# MAXREFDES117_APPS_P1.net
KiCad netlist of a schematic drawn in Altium Designer
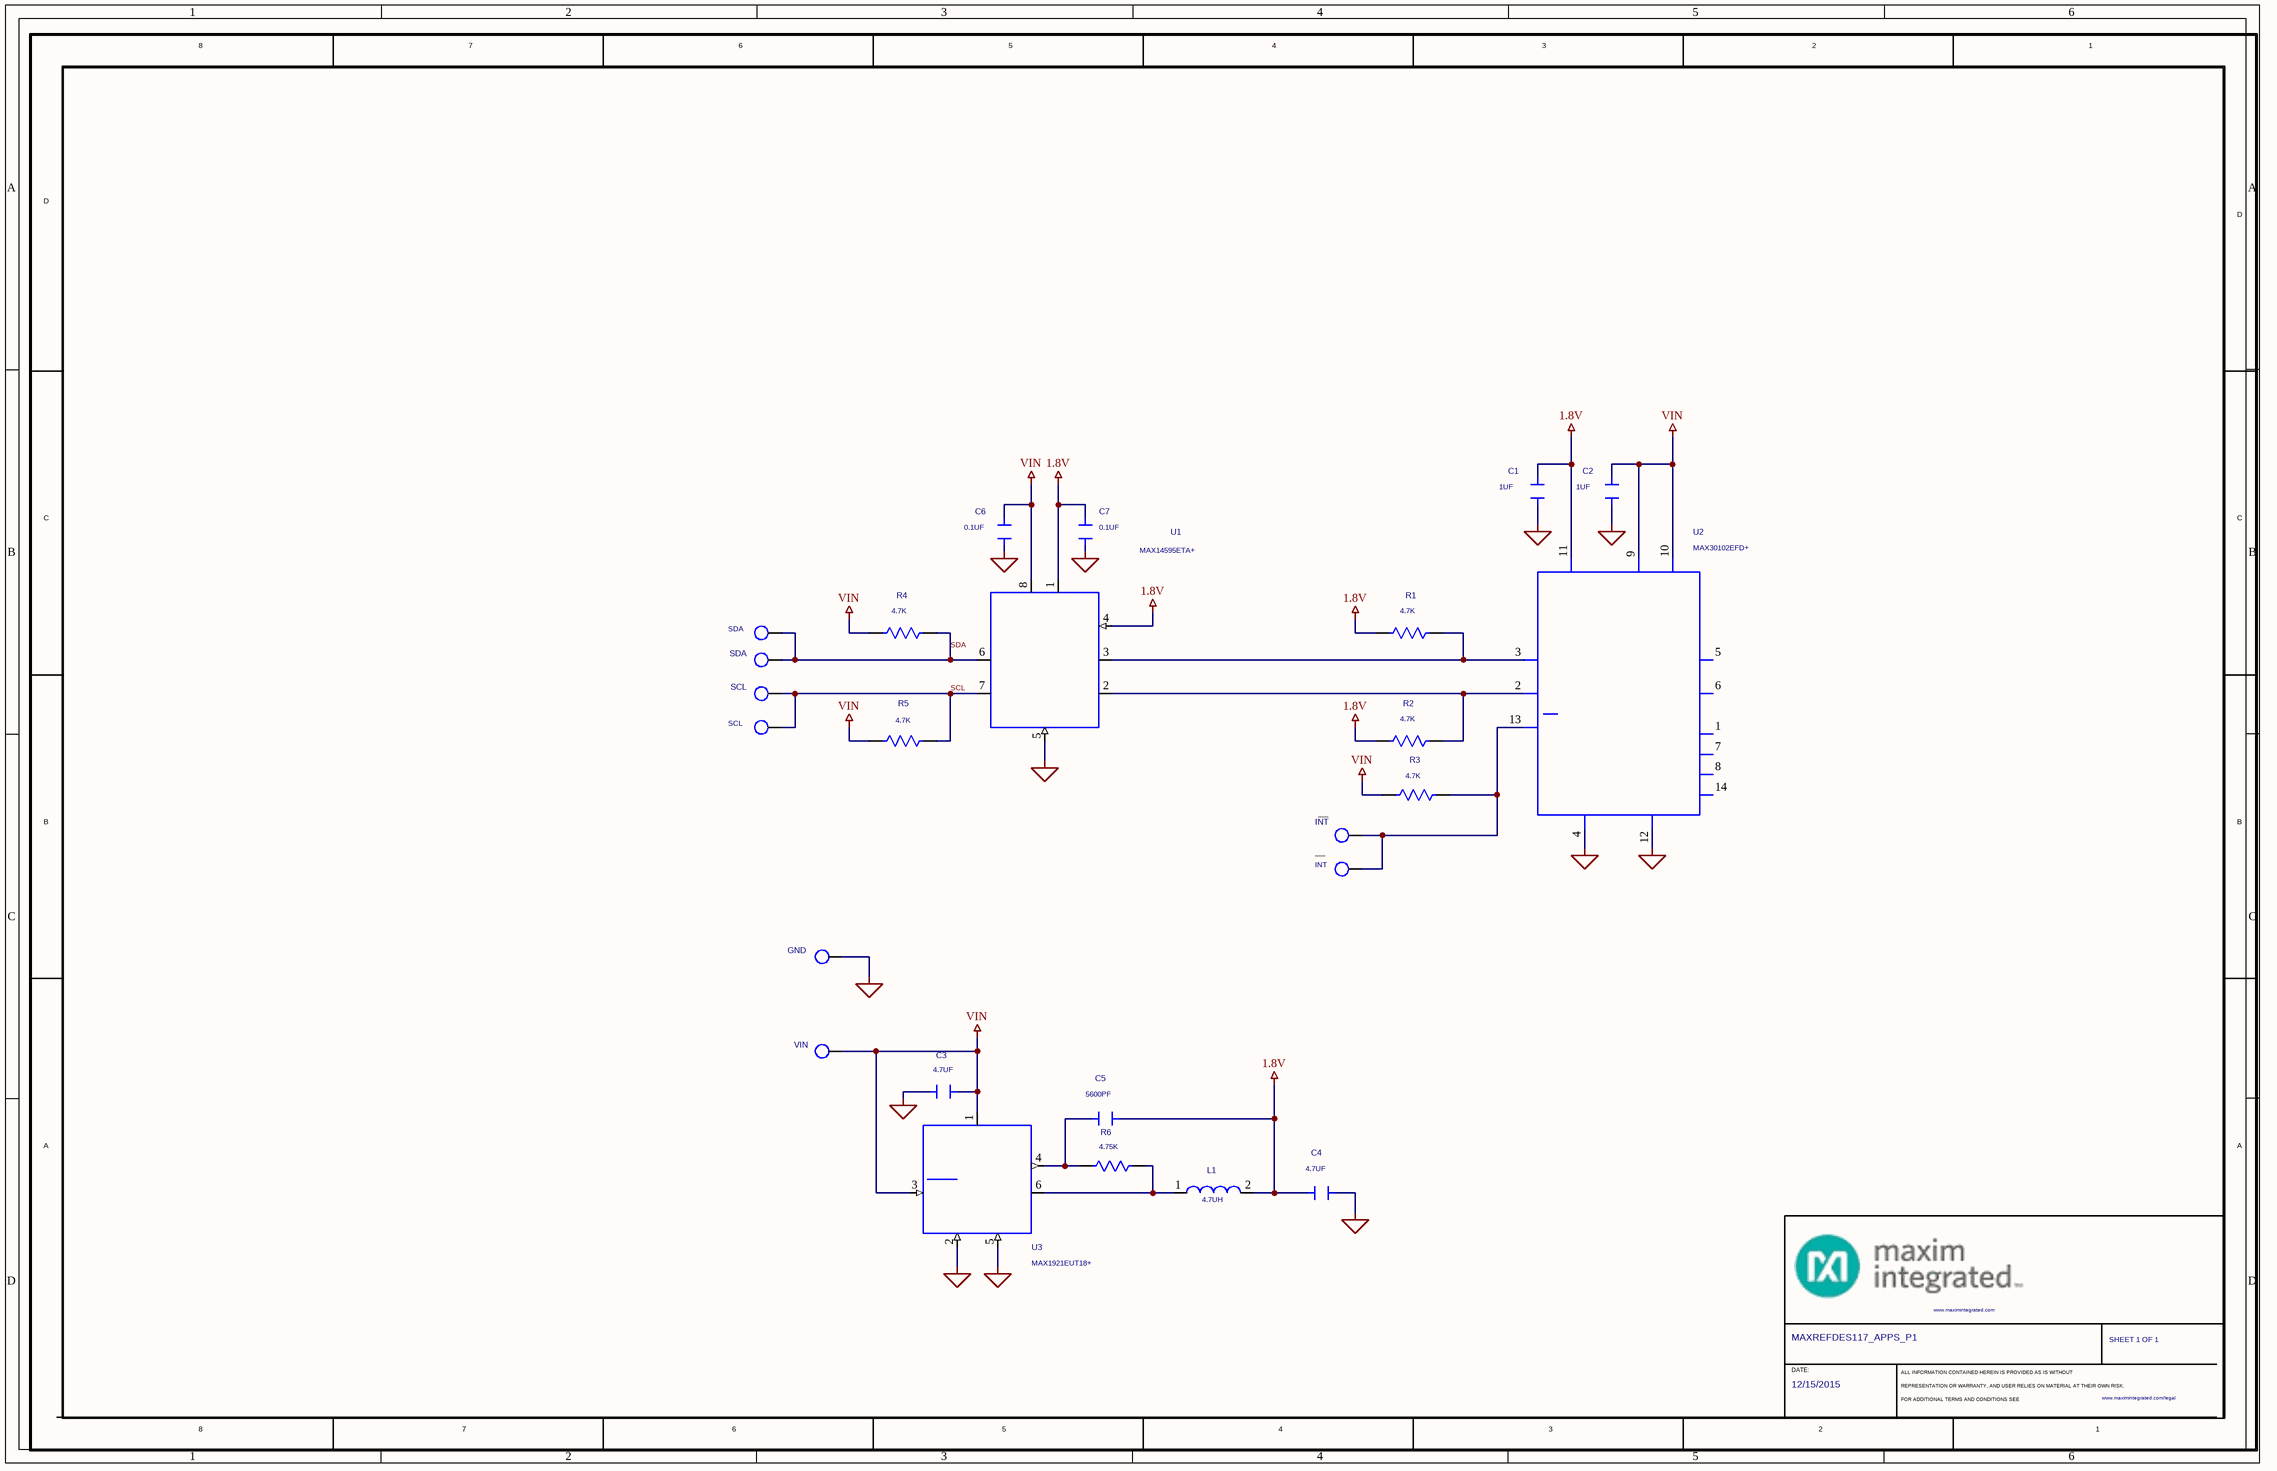
[diagram p0: MAXREFDES117_APPS_P1.SchDoc]

(export (version "E")
  (design (tool "Eeschema 10.0.6"))
  (components
    (comp (ref "*")
      (value "MAXIM_B_SIZE_CF")
      (fields
        (field (name "CUSTOM_TXT_CDS21") "SHEET 1 OF 1")
        (field (name "PROJECT_TITLE") "MAXREFDES117_APPS_P1")
        (field (name "LEAGAL_WEBLINK") "www.maximintegrated.com/legal")
        (field (name "WEBLINK1") "www.maximintegrated.com")
        (field (name "DATE") "12/15/2015")
      )
      (libsource (lib "*") (part "MAXIM_B_SIZE_CF"))
    )
    (comp (ref "C1")
      (value "1UF")
      (footprint "0402")
      (description "CAP; SMT (0402); 1UF; 10%; 10V; X5R; CERAMIC")
      (fields (field (name "TOLERANCE") "10%") (field (name "MANUFACTURER") "VENKEL LTD.;MURATA"))
      (libsource (lib "*") (part "CAP_NP#1"))
    )
    (comp (ref "C2")
      (value "1UF")
      (footprint "0402")
      (description "CAP; SMT (0402); 1UF; 10%; 10V; X5R; CERAMIC")
      (fields (field (name "TOLERANCE") "10%") (field (name "MANUFACTURER") "VENKEL LTD.;MURATA"))
      (libsource (lib "*") (part "CAP_NP#1"))
    )
    (comp (ref "C3")
      (value "4.7UF")
      (footprint "0402")
      (description "CAP; SMT (0402); 4.7UF; 20%; 4V; X5R; CERAMIC")
      (fields (field (name "TOLERANCE") "20%") (field (name "MANUFACTURER") "KEMET;MURATA;MURATA"))
      (libsource (lib "*") (part "CAP_NP"))
    )
    (comp (ref "C4")
      (value "4.7UF")
      (footprint "0402")
      (description "CAP; SMT (0402); 4.7UF; 20%; 4V; X5R; CERAMIC")
      (fields (field (name "TOLERANCE") "20%") (field (name "MANUFACTURER") "KEMET;MURATA;MURATA"))
      (libsource (lib "*") (part "CAP_NP"))
    )
    (comp (ref "C5")
      (value "5600PF")
      (footprint "0402")
      (description "CAP; SMT (0402); 5600PF; 10%; 25V; X7R; CERAMIC")
      (fields (field (name "TOLERANCE") "10%") (field (name "MANUFACTURER") "VENKEL LTD;MURATA;MURATA"))
      (libsource (lib "*") (part "CAP_NP"))
    )
    (comp (ref "C6")
      (value "0.1UF")
      (footprint "0402")
      (description "CAP; SMT (0402); 0.1UF; 10%; 16V; X7R; CERAMIC")
      (fields (field (name "TOLERANCE") "10%"))
      (libsource (lib "*") (part "CAP_NP#1"))
    )
    (comp (ref "C7")
      (value "0.1UF")
      (footprint "0402")
      (description "CAP; SMT (0402); 0.1UF; 10%; 16V; X7R; CERAMIC")
      (fields (field (name "TOLERANCE") "10%"))
      (libsource (lib "*") (part "CAP_NP#1"))
    )
    (comp (ref "GND")
      (value "N/A")
      (footprint "EK_TP_PEDGE")
      (description "TEST POINT; PAD DIMENSION =2.00MM X 2.00MM X ROUND BASE DIA=1.00 MM; BOARD HOLE= 1.02MM")
      (libsource (lib "*") (part "EVKIT_TP"))
    )
    (comp (ref "INT")
      (value "N/A")
      (footprint "EK_TP_PEDGE")
      (description "TEST POINT; PAD DIMENSION =2.00MM X 2.00MM X ROUND BASE DIA=1.00 MM; BOARD HOLE= 1.02MM")
      (libsource (lib "*") (part "EVKIT_TP"))
    )
    (comp (ref "L1")
      (value "4.7UH")
      (footprint "0603")
      (description "INDUCTOR; SMT (0603); MAGNETICALLY SHIELDED; 4.7UH; TOL=+/-20%; 0.5A")
      (fields (field (name "TOLERANCE") "20%") (field (name "MANUFACTURER") "TDK"))
      (libsource (lib "*") (part "INDUCT"))
    )
    (comp (ref "R1")
      (value "4.7K")
      (footprint "0402")
      (description "RES; SMT (0402); 4.7K; 1%; +/-100PPM/DEGC; 0.1000W")
      (fields (field (name "TOLERANCE") "1%") (field (name "MANUFACTURER") "PANASONIC"))
      (libsource (lib "*") (part "RES_SMD"))
    )
    (comp (ref "R2")
      (value "4.7K")
      (footprint "0402")
      (description "RES; SMT (0402); 4.7K; 1%; +/-100PPM/DEGC; 0.1000W")
      (fields (field (name "TOLERANCE") "1%") (field (name "MANUFACTURER") "PANASONIC"))
      (libsource (lib "*") (part "RES_SMD"))
    )
    (comp (ref "R3")
      (value "4.7K")
      (footprint "0402")
      (description "RES; SMT (0402); 4.7K; 1%; +/-100PPM/DEGC; 0.1000W")
      (fields (field (name "TOLERANCE") "1%") (field (name "MANUFACTURER") "PANASONIC"))
      (libsource (lib "*") (part "RES_SMD"))
    )
    (comp (ref "R4")
      (value "4.7K")
      (footprint "0402")
      (description "RES; SMT (0402); 4.7K; 1%; +/-100PPM/DEGC; 0.1000W")
      (fields (field (name "TOLERANCE") "1%") (field (name "MANUFACTURER") "PANASONIC"))
      (libsource (lib "*") (part "RES_SMD"))
    )
    (comp (ref "R5")
      (value "4.7K")
      (footprint "0402")
      (description "RES; SMT (0402); 4.7K; 1%; +/-100PPM/DEGC; 0.1000W")
      (fields (field (name "TOLERANCE") "1%") (field (name "MANUFACTURER") "PANASONIC"))
      (libsource (lib "*") (part "RES_SMD"))
    )
    (comp (ref "R6")
      (value "4.75K")
      (footprint "0402")
      (description "RES; SMT (0402); 4.75K; 1%; +/-100PPM/DEGC; 0.0630W")
      (fields (field (name "TOLERANCE") "1%") (field (name "MANUFACTURER") "VISHAY DALE"))
      (libsource (lib "*") (part "RES_SMD"))
    )
    (comp (ref "SCL")
      (value "N/A")
      (footprint "EK_TP_PEDGE")
      (description "TEST POINT; PAD DIMENSION =2.00MM X 2.00MM X ROUND BASE DIA=1.00 MM; BOARD HOLE= 1.02MM")
      (libsource (lib "*") (part "EVKIT_TP"))
    )
    (comp (ref "SDA")
      (value "N/A")
      (footprint "EK_TP_PEDGE")
      (description "TEST POINT; PAD DIMENSION =2.00MM X 2.00MM X ROUND BASE DIA=1.00 MM; BOARD HOLE= 1.02MM")
      (libsource (lib "*") (part "EVKIT_TP"))
    )
    (comp (ref "U1")
      (value "MAX14595ETA+")
      (footprint "MAXIM_90-0349")
      (description "IC; TRANS; LOW-POWER DUAL-CHANNEL LOGIC-LEVEL TRANSLATOR; TDFN8 2X2")
      (fields (field (name "MANUFACTURER") "MAXIM"))
      (libsource (lib "*") (part "MAX14595"))
    )
    (comp (ref "U2")
      (value "MAX30102EFD+")
      (footprint "PSON80P560X330X165-14M")
      (fields (field (name "MANUFACTURER") "MAXIM"))
      (libsource (lib "*") (part "MAX30102"))
    )
    (comp (ref "U3")
      (value "MAX1921EUT18+")
      (footprint "SOT95P280X145-6M")
      (description "IC; CONV; LOW-VOLTAGE; 400MA STEP-DOWN DC-DC CONVERTER; SOT23-6")
      (fields (field (name "MANUFACTURER") "MAXIM"))
      (libsource (lib "*") (part "MAX1921"))
    )
    (comp (ref "VIN")
      (value "N/A")
      (footprint "EK_TP_PEDGE")
      (description "TEST POINT; PAD DIMENSION =2.00MM X 2.00MM X ROUND BASE DIA=1.00 MM; BOARD HOLE= 1.02MM")
      (libsource (lib "*") (part "EVKIT_TP"))
    )
    (comp (ref "X1")
      (value "N/A")
      (footprint "EK_TP_PEDGE")
      (description "TEST POINT; PAD DIMENSION =2.00MM X 2.00MM X ROUND BASE DIA=1.00 MM; BOARD HOLE= 1.02MM")
      (fields (field (name "COMMENTS") "SDA"))
      (libsource (lib "*") (part "EVKIT_TP"))
    )
    (comp (ref "X2")
      (value "N/A")
      (footprint "EK_TP_PEDGE")
      (description "TEST POINT; PAD DIMENSION =2.00MM X 2.00MM X ROUND BASE DIA=1.00 MM; BOARD HOLE= 1.02MM")
      (fields (field (name "COMMENTS") "SCL"))
      (libsource (lib "*") (part "EVKIT_TP"))
    )
    (comp (ref "X3")
      (value "N/A")
      (footprint "EK_TP_PEDGE")
      (description "TEST POINT; PAD DIMENSION =2.00MM X 2.00MM X ROUND BASE DIA=1.00 MM; BOARD HOLE= 1.02MM")
      (fields (field (name "COMMENTS") "INT"))
      (libsource (lib "*") (part "EVKIT_TP"))
    )
  )
  (nets
    (net (code "1") (name "/SCL") (class "Default")
      (node (ref "R5") (pin "2") (pinfunction "2_2") (pintype "bidirectional"))
      (node (ref "SCL") (pin "1") (pinfunction "TP1_1") (pintype "bidirectional"))
      (node (ref "U1") (pin "7") (pinfunction "IOVCC2_7") (pintype "bidirectional"))
      (node (ref "X2") (pin "1") (pinfunction "TP1_1") (pintype "bidirectional"))
    )
    (net (code "2") (name "/SDA") (class "Default")
      (node (ref "R4") (pin "2") (pinfunction "2_2") (pintype "bidirectional"))
      (node (ref "SDA") (pin "1") (pinfunction "TP1_1") (pintype "bidirectional"))
      (node (ref "U1") (pin "6") (pinfunction "IOVCC1_6") (pintype "bidirectional"))
      (node (ref "X1") (pin "1") (pinfunction "TP1_1") (pintype "bidirectional"))
    )
    (net (code "3") (name "1.8V") (class "Default")
      (node (ref "C1") (pin "2") (pinfunction "2_2") (pintype "bidirectional"))
      (node (ref "C4") (pin "1") (pinfunction "1_1") (pintype "bidirectional"))
      (node (ref "C5") (pin "2") (pinfunction "2_2") (pintype "bidirectional"))
      (node (ref "C7") (pin "2") (pinfunction "2_2") (pintype "bidirectional"))
      (node (ref "L1") (pin "2") (pinfunction "2_2") (pintype "bidirectional"))
      (node (ref "R1") (pin "1") (pinfunction "1_1") (pintype "bidirectional"))
      (node (ref "R2") (pin "1") (pinfunction "1_1") (pintype "bidirectional"))
      (node (ref "U1") (pin "1") (pinfunction "VL_1") (pintype "bidirectional"))
      (node (ref "U1") (pin "4") (pinfunction "/TS_4") (pintype "input"))
      (node (ref "U2") (pin "11") (pinfunction "VDD_11") (pintype "bidirectional"))
    )
    (net (code "4") (name "GND_SIGNAL") (class "Default")
      (node (ref "C1") (pin "1") (pinfunction "1_1") (pintype "bidirectional"))
      (node (ref "C2") (pin "1") (pinfunction "1_1") (pintype "bidirectional"))
      (node (ref "C3") (pin "1") (pinfunction "1_1") (pintype "bidirectional"))
      (node (ref "C4") (pin "2") (pinfunction "2_2") (pintype "bidirectional"))
      (node (ref "C6") (pin "1") (pinfunction "1_1") (pintype "bidirectional"))
      (node (ref "C7") (pin "1") (pinfunction "1_1") (pintype "bidirectional"))
      (node (ref "GND") (pin "1") (pinfunction "TP1_1") (pintype "bidirectional"))
      (node (ref "U1") (pin "5") (pinfunction "GND_5") (pintype "input"))
      (node (ref "U2") (pin "12") (pinfunction "GND_12") (pintype "input"))
      (node (ref "U2") (pin "4") (pinfunction "PGND_4") (pintype "input"))
      (node (ref "U3") (pin "2") (pinfunction "AGND_2") (pintype "input"))
      (node (ref "U3") (pin "5") (pinfunction "PGND_5") (pintype "input"))
    )
    (net (code "5") (name "Net-(INT-TP1)") (class "Default")
      (node (ref "INT") (pin "1") (pinfunction "TP1_1") (pintype "bidirectional"))
      (node (ref "R3") (pin "2") (pinfunction "2_2") (pintype "bidirectional"))
      (node (ref "U2") (pin "13") (pinfunction "/INT_13") (pintype "input"))
      (node (ref "X3") (pin "1") (pinfunction "TP1_1") (pintype "bidirectional"))
    )
    (net (code "6") (name "Net-(U1-IOVL1)") (class "Default")
      (node (ref "R1") (pin "2") (pinfunction "2_2") (pintype "bidirectional"))
      (node (ref "U1") (pin "3") (pinfunction "IOVL1_3") (pintype "bidirectional"))
      (node (ref "U2") (pin "3") (pinfunction "SDA_3") (pintype "bidirectional"))
    )
    (net (code "7") (name "Net-(U1-IOVL2)") (class "Default")
      (node (ref "R2") (pin "2") (pinfunction "2_2") (pintype "bidirectional"))
      (node (ref "U1") (pin "2") (pinfunction "IOVL2_2") (pintype "bidirectional"))
      (node (ref "U2") (pin "2") (pinfunction "SCL_2") (pintype "input"))
    )
    (net (code "8") (name "Net-(U3-LX)") (class "Default")
      (node (ref "L1") (pin "1") (pinfunction "1_1") (pintype "bidirectional"))
      (node (ref "R6") (pin "2") (pinfunction "2_2") (pintype "bidirectional"))
      (node (ref "U3") (pin "6") (pinfunction "LX_6") (pintype "bidirectional"))
    )
    (net (code "9") (name "Net-(U3-OUT)") (class "Default")
      (node (ref "C5") (pin "1") (pinfunction "1_1") (pintype "bidirectional"))
      (node (ref "R6") (pin "1") (pinfunction "1_1") (pintype "bidirectional"))
      (node (ref "U3") (pin "4") (pinfunction "OUT_4") (pintype "output"))
    )
    (net (code "10") (name "VIN") (class "Default")
      (node (ref "C2") (pin "2") (pinfunction "2_2") (pintype "bidirectional"))
      (node (ref "C3") (pin "2") (pinfunction "2_2") (pintype "bidirectional"))
      (node (ref "C6") (pin "2") (pinfunction "2_2") (pintype "bidirectional"))
      (node (ref "R3") (pin "1") (pinfunction "1_1") (pintype "bidirectional"))
      (node (ref "R4") (pin "1") (pinfunction "1_1") (pintype "bidirectional"))
      (node (ref "R5") (pin "1") (pinfunction "1_1") (pintype "bidirectional"))
      (node (ref "U1") (pin "8") (pinfunction "VCC_8") (pintype "bidirectional"))
      (node (ref "U2") (pin "10") (pinfunction "VLED+_2_10") (pintype "bidirectional"))
      (node (ref "U2") (pin "9") (pinfunction "VLED+_1_9") (pintype "bidirectional"))
      (node (ref "U3") (pin "1") (pinfunction "IN_1") (pintype "bidirectional"))
      (node (ref "U3") (pin "3") (pinfunction "/SHDN_3") (pintype "input"))
      (node (ref "VIN") (pin "1") (pinfunction "TP1_1") (pintype "bidirectional"))
    )
    (net (code "11") (name "unconnected-(U2-IR_DRV-Pad6)") (class "Default")
      (node (ref "U2") (pin "6") (pinfunction "IR_DRV_6") (pintype "bidirectional"))
    )
    (net (code "12") (name "unconnected-(U2-NC_1-Pad1)") (class "Default")
      (node (ref "U2") (pin "1") (pinfunction "NC_1_1") (pintype "bidirectional"))
    )
    (net (code "13") (name "unconnected-(U2-NC_2-Pad7)") (class "Default")
      (node (ref "U2") (pin "7") (pinfunction "NC_2_7") (pintype "bidirectional"))
    )
    (net (code "14") (name "unconnected-(U2-NC_3-Pad8)") (class "Default")
      (node (ref "U2") (pin "8") (pinfunction "NC_3_8") (pintype "bidirectional"))
    )
    (net (code "15") (name "unconnected-(U2-NC_4-Pad14)") (class "Default")
      (node (ref "U2") (pin "14") (pinfunction "NC_4_14") (pintype "bidirectional"))
    )
    (net (code "16") (name "unconnected-(U2-R_DRV-Pad5)") (class "Default")
      (node (ref "U2") (pin "5") (pinfunction "R_DRV_5") (pintype "bidirectional"))
    )
  )
)
